# Halcyon_Audio_Mixer.net
KiCad netlist of a schematic drawn in EAGLE
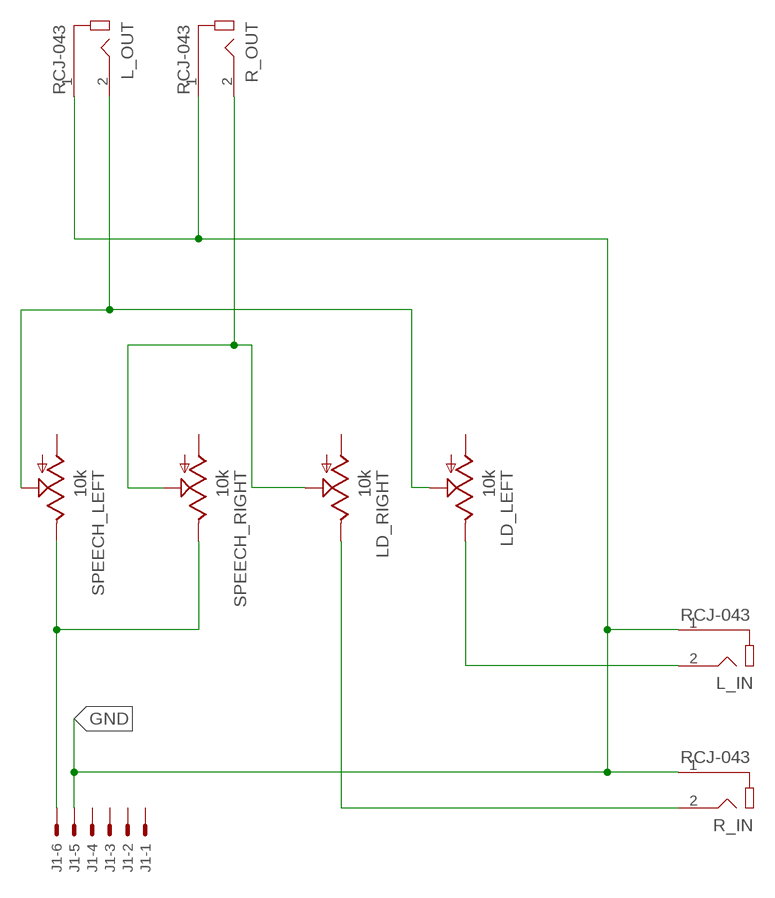
[diagram p0: schematic, sheet 1]

(export (version "E")
  (design (tool "Eeschema 10.0.6"))
  (components
    (comp (ref "J1")
      (value "22-23-2061")
      (footprint "eagle-import:22-23-2061")
      (fields (field (name "MF") "MOLEX"))
      (libsource (lib "eagle-import") (part "22-23-2061"))
    )
    (comp (ref "LD_LEFT")
      (value "10k")
      (footprint "eagle-import:B25P")
      (libsource (lib "eagle-import") (part "TRIM_US-B25P"))
    )
    (comp (ref "LD_RIGHT")
      (value "10k")
      (footprint "eagle-import:B25P")
      (libsource (lib "eagle-import") (part "TRIM_US-B25P"))
    )
    (comp (ref "L_IN")
      (value "RCJ-043")
      (footprint "eagle-import:CUI_RCJ-043")
      (fields (field (name "MF") "CUI Devices"))
      (libsource (lib "eagle-import") (part "RCJ-043"))
    )
    (comp (ref "L_OUT")
      (value "RCJ-043")
      (footprint "eagle-import:CUI_RCJ-043")
      (fields (field (name "MF") "CUI Devices"))
      (libsource (lib "eagle-import") (part "RCJ-043"))
    )
    (comp (ref "R_IN")
      (value "RCJ-043")
      (footprint "eagle-import:CUI_RCJ-043")
      (fields (field (name "MF") "CUI Devices"))
      (libsource (lib "eagle-import") (part "RCJ-043"))
    )
    (comp (ref "R_OUT")
      (value "RCJ-043")
      (footprint "eagle-import:CUI_RCJ-043")
      (fields (field (name "MF") "CUI Devices"))
      (libsource (lib "eagle-import") (part "RCJ-043"))
    )
    (comp (ref "SPEECH_LEFT")
      (value "10k")
      (footprint "eagle-import:B25P")
      (libsource (lib "eagle-import") (part "TRIM_US-B25P"))
    )
    (comp (ref "SPEECH_RIGHT")
      (value "10k")
      (footprint "eagle-import:B25P")
      (libsource (lib "eagle-import") (part "TRIM_US-B25P"))
    )
  )
  (nets
    (net (code "1") (name "GND") (class "Default")
      (node (ref "J1") (pin "5") (pinfunction "S_5") (pintype "passive"))
      (node (ref "L_IN") (pin "1") (pinfunction "1_1") (pintype "passive"))
      (node (ref "L_OUT") (pin "1") (pinfunction "1_1") (pintype "passive"))
      (node (ref "R_IN") (pin "1") (pinfunction "1_1") (pintype "passive"))
      (node (ref "R_OUT") (pin "1") (pinfunction "1_1") (pintype "passive"))
    )
    (net (code "2") (name "Net-(J1F-S)") (class "Default")
      (node (ref "J1") (pin "6") (pinfunction "S_6") (pintype "passive"))
      (node (ref "SPEECH_LEFT") (pin "E") (pinfunction "E_E") (pintype "passive"))
      (node (ref "SPEECH_RIGHT") (pin "E") (pinfunction "E_E") (pintype "passive"))
    )
    (net (code "3") (name "Net-(LD_LEFT-PadE)") (class "Default")
      (node (ref "LD_LEFT") (pin "E") (pinfunction "E_E") (pintype "passive"))
      (node (ref "L_IN") (pin "2") (pinfunction "2_2") (pintype "passive"))
    )
    (net (code "4") (name "Net-(LD_LEFT-PadS)") (class "Default")
      (node (ref "LD_LEFT") (pin "S") (pinfunction "S_S") (pintype "passive"))
      (node (ref "L_OUT") (pin "2") (pinfunction "2_2") (pintype "passive"))
      (node (ref "SPEECH_LEFT") (pin "S") (pinfunction "S_S") (pintype "passive"))
    )
    (net (code "5") (name "Net-(LD_RIGHT-PadE)") (class "Default")
      (node (ref "LD_RIGHT") (pin "E") (pinfunction "E_E") (pintype "passive"))
      (node (ref "R_IN") (pin "2") (pinfunction "2_2") (pintype "passive"))
    )
    (net (code "6") (name "Net-(LD_RIGHT-PadS)") (class "Default")
      (node (ref "LD_RIGHT") (pin "S") (pinfunction "S_S") (pintype "passive"))
      (node (ref "R_OUT") (pin "2") (pinfunction "2_2") (pintype "passive"))
      (node (ref "SPEECH_RIGHT") (pin "S") (pinfunction "S_S") (pintype "passive"))
    )
    (net (code "7") (name "unconnected-(J1A-S-Pad1)") (class "Default")
      (node (ref "J1") (pin "1") (pinfunction "S_1") (pintype "passive"))
    )
    (net (code "8") (name "unconnected-(J1B-S-Pad2)") (class "Default")
      (node (ref "J1") (pin "2") (pinfunction "S_2") (pintype "passive"))
    )
    (net (code "9") (name "unconnected-(J1C-S-Pad3)") (class "Default")
      (node (ref "J1") (pin "3") (pinfunction "S_3") (pintype "passive"))
    )
    (net (code "10") (name "unconnected-(J1D-S-Pad4)") (class "Default")
      (node (ref "J1") (pin "4") (pinfunction "S_4") (pintype "passive"))
    )
    (net (code "11") (name "unconnected-(LD_LEFT-PadA)") (class "Default")
      (node (ref "LD_LEFT") (pin "A") (pinfunction "A_A") (pintype "passive"))
    )
    (net (code "12") (name "unconnected-(LD_RIGHT-PadA)") (class "Default")
      (node (ref "LD_RIGHT") (pin "A") (pinfunction "A_A") (pintype "passive"))
    )
    (net (code "13") (name "unconnected-(SPEECH_LEFT-PadA)") (class "Default")
      (node (ref "SPEECH_LEFT") (pin "A") (pinfunction "A_A") (pintype "passive"))
    )
    (net (code "14") (name "unconnected-(SPEECH_RIGHT-PadA)") (class "Default")
      (node (ref "SPEECH_RIGHT") (pin "A") (pinfunction "A_A") (pintype "passive"))
    )
  )
)
